# PowerSupplies.net
KiCad netlist of a schematic drawn in Altium Designer
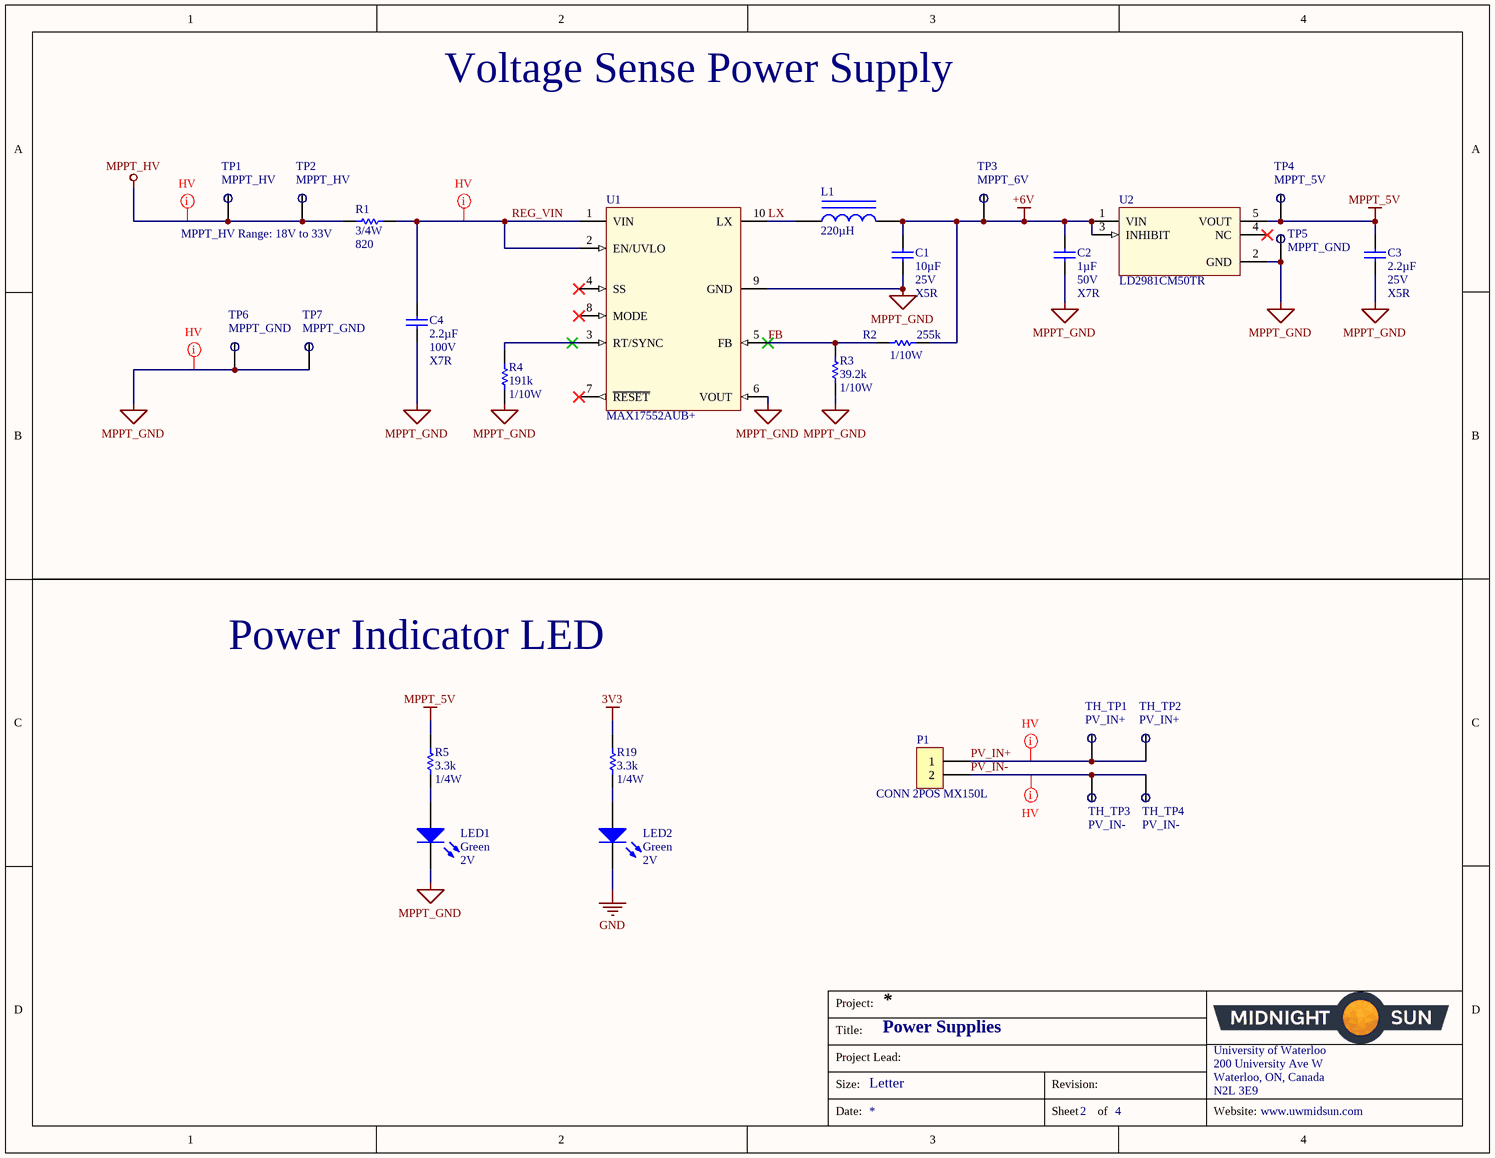
[diagram p0: PowerSupplies.SchDoc]

(export (version "E")
  (design (tool "Eeschema 10.0.6"))
  (components
    (comp (ref "C1")
      (value "CAP CER 10uF 25V 20% X5R 0603")
      (footprint "CAP, 0603")
      (description "10µF ±20% 25V Ceramic Capacitor X5R 0603 (1608 Metric)")
      (fields
        (field (name "TOLERANCE") "±20%")
        (field (name "CAPACITANCE") "10µF")
        (field (name "VOLTAGE") "25V")
        (field (name "TEMPERATURE COEFFICIENT") "X5R")
      )
      (libsource (lib "Schematic Diagrams") (part "CAP CER 10uF 25V 20% X5R 0603"))
    )
    (comp (ref "C2")
      (value "CAP CER 1UF 50V 10% X7R 0603")
      (footprint "CAP, 0603")
      (description "1µF ±10% 50V Ceramic Capacitor X7R 0603 (1608 Metric)")
      (fields
        (field (name "TOLERANCE") "±10%")
        (field (name "CAPACITANCE") "1µF")
        (field (name "VOLTAGE") "50V")
        (field (name "TEMPERATURE COEFFICIENT") "X7R")
      )
      (libsource (lib "Schematic Diagrams") (part "CAP CER 1UF 50V 10% X7R 0603"))
    )
    (comp (ref "C3")
      (value "CAP CER 2.2UF 25V 10% X5R 0603")
      (footprint "CAP, 0603")
      (description "2.2µF ±10% 25V Ceramic Capacitor X5R 0603 (1608 Metric)")
      (fields
        (field (name "TOLERANCE") "±10%")
        (field (name "CAPACITANCE") "2.2µF")
        (field (name "VOLTAGE") "25V")
        (field (name "TEMPERATURE COEFFICIENT") "X5R")
      )
      (libsource (lib "Schematic Diagrams") (part "CAP CER 2.2UF 25V 10% X5R 0603"))
    )
    (comp (ref "C4")
      (value "CAP CER 2.2UF 100V ±20% X7R 1206")
      (footprint "CAP, 1206")
      (description "2.2µF ±20% 100V Ceramic Capacitor X7R 1206 (3216 Metric)")
      (fields
        (field (name "TOLERANCE") "±20%")
        (field (name "CAPACITANCE") "2.2µF")
        (field (name "VOLTAGE") "100V")
        (field (name "TEMPERATURE COEFFICIENT") "X7R")
      )
      (libsource (lib "Schematic Diagrams") (part "CAP CER 2.2UF 100V ±20% X7R 1206"))
    )
    (comp (ref "L1")
      (value "IND 220uH 0.59A 20%")
      (footprint "INDP6060X23N")
      (description "220µH Shielded Inductor 590mA 834 mOhm Nonstandard")
      (fields (field (name "TOLERANCE") "±20%") (field (name "INDUCTANCE") "220µH"))
      (libsource (lib "Schematic Diagrams") (part "IND 220uH 0.59A 20%"))
    )
    (comp (ref "LED1")
      (value "LED GREEN CLEAR 2V 0603")
      (footprint "LED_0603")
      (description "Green 572nm LED Indication - Discrete 2V 0603 (1608 Metric)")
      (fields
        (field (name "MANUFACTURER") "Wurth Electronics Inc.")
        (field (name "MANUFACTURER PART NUMBER") "150060VS75000")
        (field (name "COLOR") "Green")
        (field (name "VOLTAGE - FORWARD (VF) (TYP)") "2V")
      )
      (libsource (lib "Schematic Diagrams") (part "LED GREEN CLEAR 2V 0603"))
    )
    (comp (ref "LED2")
      (value "LED GREEN CLEAR 2V 0603")
      (footprint "LED_0603")
      (description "Green 572nm LED Indication - Discrete 2V 0603 (1608 Metric)")
      (fields
        (field (name "MANUFACTURER") "Wurth Electronics Inc.")
        (field (name "MANUFACTURER PART NUMBER") "150060VS75000")
        (field (name "COLOR") "Green")
        (field (name "VOLTAGE - FORWARD (VF) (TYP)") "2V")
      )
      (libsource (lib "Schematic Diagrams") (part "LED GREEN CLEAR 2V 0603"))
    )
    (comp (ref "P1")
      (value "CONN 2POS MX150L")
      (footprint "CONN, 2POS MX150L")
      (description "Connector Header Panel Mount, Through Hole, Right Angle 2 position 0.230\" (5.84mm)")
      (fields
        (field (name "MANUFACTURER") "Molex, LLC")
        (field (name "MANUFACTURER PART NUMBER") "0194270109")
      )
      (libsource (lib "Schematic Diagrams") (part "CONN 2POS MX150L"))
    )
    (comp (ref "R1")
      (value "RES 820 OHM 5% 3/4W 2010")
      (footprint "RES 2010")
      (description "820 Ohms ±5% 0.75W, 3/4W Chip Resistor 2010 (5025 Metric) Automotive AEC-Q200 Thick Film")
      (fields
        (field (name "MANUFACTURER") "Stackpole Electronics Inc.")
        (field (name "MANUFACTURER PART NUMBER") "RMCF2010JT820R")
        (field (name "POWER") "3/4W")
        (field (name "RESISTANCE") "820")
      )
      (libsource (lib "Schematic Diagrams") (part "RES 820 OHM 5% 3/4W 2010"))
    )
    (comp (ref "R2")
      (value "RES 255K OHM 1% 1/10W 0603")
      (footprint "RES, 0603")
      (description "255k Ohm ±1% 0.1W, 1/10W Chip Resistor 0603 (1608 Metric) Moisture Resistant Thick Film")
      (fields
        (field (name "TOLERANCE") "±1%")
        (field (name "RESISTANCE (OHMS)") "255k")
        (field (name "POWER (WATTS)") "1/10W")
      )
      (libsource (lib "Schematic Diagrams") (part "RES 255K OHM 1% 1/10W 0603"))
    )
    (comp (ref "R3")
      (value "RES 39.2K OHM 1% 1/10W 0603")
      (footprint "RES, 0603")
      (description "39.2k Ohm ±1% 0.1W, 1/10W Chip Resistor 0603 (1608 Metric) Moisture Resistant Thick Film")
      (fields
        (field (name "TOLERANCE") "±1%")
        (field (name "RESISTANCE") "39.2k")
        (field (name "POWER") "1/10W")
      )
      (libsource (lib "Schematic Diagrams") (part "RES 39.2K OHM 1% 1/10W 0603"))
    )
    (comp (ref "R4")
      (value "RES 191K OHM 1% 1/10W 0603")
      (footprint "RES, 0603")
      (description "191k Ohm ±1% 0.1W, 1/10W Chip Resistor 0603 (1608 Metric) Moisture Resistant Thick Film")
      (fields
        (field (name "RESISTANCE") "191k")
        (field (name "TOLERANCE") "±1%")
        (field (name "POWER") "1/10W")
      )
      (libsource (lib "Schematic Diagrams") (part "RES 191K OHM 1% 1/10W 0603"))
    )
    (comp (ref "R5")
      (value "RES 3.3K OHM 1% 1/4W 0603")
      (footprint "RES, 0603")
      (fields
        (field (name "TOLERANCE") "±1%")
        (field (name "RESISTANCE") "3.3k")
        (field (name "POWER") "1/4W")
      )
      (libsource (lib "Schematic Diagrams") (part "RES 3.3K OHM 1% 1/4W 0603"))
    )
    (comp (ref "R19")
      (value "RES 3.3K OHM 1% 1/4W 0603")
      (footprint "RES, 0603")
      (fields
        (field (name "TOLERANCE") "±1%")
        (field (name "RESISTANCE") "3.3k")
        (field (name "POWER") "1/4W")
      )
      (libsource (lib "Schematic Diagrams") (part "RES 3.3K OHM 1% 1/4W 0603"))
    )
    (comp (ref "TH_TP1")
      (value "PV_IN+")
      (footprint "Thru Test Point")
      (libsource (lib "Schematic Diagrams") (part "Thru Test Point"))
    )
    (comp (ref "TH_TP2")
      (value "PV_IN+")
      (footprint "Thru Test Point")
      (libsource (lib "Schematic Diagrams") (part "Thru Test Point"))
    )
    (comp (ref "TH_TP3")
      (value "PV_IN-")
      (footprint "Thru Test Point")
      (libsource (lib "Schematic Diagrams") (part "Thru Test Point"))
    )
    (comp (ref "TH_TP4")
      (value "PV_IN-")
      (footprint "Thru Test Point")
      (libsource (lib "Schematic Diagrams") (part "Thru Test Point"))
    )
    (comp (ref "TP1")
      (value "MPPT_HV")
      (footprint "Thru Test Point")
      (libsource (lib "Schematic Diagrams") (part "Thru Test Point"))
    )
    (comp (ref "TP2")
      (value "MPPT_HV")
      (footprint "Thru Test Point")
      (libsource (lib "Schematic Diagrams") (part "Thru Test Point"))
    )
    (comp (ref "TP3")
      (value "MPPT_6V")
      (footprint "Thru Test Point")
      (libsource (lib "Schematic Diagrams") (part "Thru Test Point"))
    )
    (comp (ref "TP4")
      (value "MPPT_5V")
      (footprint "Thru Test Point")
      (libsource (lib "Schematic Diagrams") (part "Thru Test Point"))
    )
    (comp (ref "TP5")
      (value "MPPT_GND")
      (footprint "Thru Test Point")
      (libsource (lib "Schematic Diagrams") (part "Thru Test Point"))
    )
    (comp (ref "TP6")
      (value "MPPT_GND")
      (footprint "Thru Test Point")
      (libsource (lib "Schematic Diagrams") (part "Thru Test Point"))
    )
    (comp (ref "TP7")
      (value "MPPT_GND")
      (footprint "Thru Test Point")
      (libsource (lib "Schematic Diagrams") (part "Thru Test Point"))
    )
    (comp (ref "U1")
      (value "IC REG BUCK ADJ 0.1A 10UMAX")
      (footprint "TSSOP50P490X110-10N")
      (fields (field (name "MANUFACTURER PART NUMBER 1") "MAX17552AUB+"))
      (libsource (lib "Schematic Diagrams") (part "IC REG BUCK ADJ 0.1A 10UMAX"))
    )
    (comp (ref "U2")
      (value "IC REG LDO 5V 0.1A SOT23-5")
      (footprint "SOT95P280X145-5N")
      (description "Linear Voltage Regulator IC Positive Fixed Output 5V 100mA SOT-23-5")
      (fields (field (name "MANUFACTURER PART NUMBER 1") "LD2981CM50TR"))
      (libsource (lib "Schematic Diagrams") (part "IC REG LDO 5V 0.1A SOT23-5"))
    )
  )
  (nets
    (net (code "1") (name "+6V") (class "Default")
      (node (ref "C1") (pin "1") (pinfunction "1_1") (pintype "passive"))
      (node (ref "C2") (pin "1") (pinfunction "1_1") (pintype "passive"))
      (node (ref "L1") (pin "2") (pinfunction "2_2") (pintype "passive"))
      (node (ref "R2") (pin "2") (pinfunction "2_2") (pintype "passive"))
      (node (ref "TP3") (pin "TH_TP") (pinfunction "1_TH_TP") (pintype "passive"))
      (node (ref "U2") (pin "1") (pinfunction "VIN_1") (pintype "power_in"))
      (node (ref "U2") (pin "3") (pinfunction "INHIBIT_3") (pintype "input"))
    )
    (net (code "2") (name "/FB") (class "Default")
      (node (ref "R2") (pin "1") (pinfunction "1_1") (pintype "passive"))
      (node (ref "R3") (pin "1") (pinfunction "1_1") (pintype "passive"))
      (node (ref "U1") (pin "5") (pinfunction "FB_5") (pintype "input"))
    )
    (net (code "3") (name "/LX") (class "Default")
      (node (ref "L1") (pin "1") (pinfunction "1_1") (pintype "passive"))
      (node (ref "U1") (pin "10") (pinfunction "LX_10") (pintype "power_in"))
    )
    (net (code "4") (name "/PV_IN+") (class "Default")
      (node (ref "P1") (pin "1") (pinfunction "1_1") (pintype "passive"))
      (node (ref "TH_TP1") (pin "TH_TP") (pinfunction "1_TH_TP") (pintype "passive"))
      (node (ref "TH_TP2") (pin "TH_TP") (pinfunction "1_TH_TP") (pintype "passive"))
    )
    (net (code "5") (name "/PV_IN-") (class "Default")
      (node (ref "P1") (pin "2") (pinfunction "2_2") (pintype "passive"))
      (node (ref "TH_TP3") (pin "TH_TP") (pinfunction "1_TH_TP") (pintype "passive"))
      (node (ref "TH_TP4") (pin "TH_TP") (pinfunction "1_TH_TP") (pintype "passive"))
    )
    (net (code "6") (name "/REG_VIN") (class "Default")
      (node (ref "C4") (pin "1") (pinfunction "1_1") (pintype "passive"))
      (node (ref "R1") (pin "2") (pinfunction "2_2") (pintype "passive"))
      (node (ref "U1") (pin "1") (pinfunction "VIN_1") (pintype "power_in"))
      (node (ref "U1") (pin "2") (pinfunction "EN/UVLO_2") (pintype "input"))
    )
    (net (code "7") (name "3V3") (class "Default")
      (node (ref "R19") (pin "1") (pinfunction "1_1") (pintype "passive"))
    )
    (net (code "8") (name "GND") (class "Default")
      (node (ref "LED2") (pin "2") (pinfunction "K_2") (pintype "passive"))
    )
    (net (code "9") (name "MPPT_5V") (class "Default")
      (node (ref "C3") (pin "1") (pinfunction "1_1") (pintype "passive"))
      (node (ref "R5") (pin "1") (pinfunction "1_1") (pintype "passive"))
      (node (ref "TP4") (pin "TH_TP") (pinfunction "1_TH_TP") (pintype "passive"))
      (node (ref "U2") (pin "5") (pinfunction "VOUT_5") (pintype "power_in"))
    )
    (net (code "10") (name "MPPT_GND") (class "Default")
      (node (ref "C1") (pin "2") (pinfunction "2_2") (pintype "passive"))
      (node (ref "C2") (pin "2") (pinfunction "2_2") (pintype "passive"))
      (node (ref "C3") (pin "2") (pinfunction "2_2") (pintype "passive"))
      (node (ref "C4") (pin "2") (pinfunction "2_2") (pintype "passive"))
      (node (ref "LED1") (pin "2") (pinfunction "K_2") (pintype "passive"))
      (node (ref "R3") (pin "2") (pinfunction "2_2") (pintype "passive"))
      (node (ref "R4") (pin "2") (pinfunction "2_2") (pintype "passive"))
      (node (ref "TP5") (pin "TH_TP") (pinfunction "1_TH_TP") (pintype "passive"))
      (node (ref "TP6") (pin "TH_TP") (pinfunction "1_TH_TP") (pintype "passive"))
      (node (ref "TP7") (pin "TH_TP") (pinfunction "1_TH_TP") (pintype "passive"))
      (node (ref "U1") (pin "6") (pinfunction "VOUT_6") (pintype "input"))
      (node (ref "U1") (pin "9") (pinfunction "GND_9") (pintype "power_in"))
      (node (ref "U2") (pin "2") (pinfunction "GND_2") (pintype "power_in"))
    )
    (net (code "11") (name "MPPT_HV") (class "Default")
      (node (ref "R1") (pin "1") (pinfunction "1_1") (pintype "passive"))
      (node (ref "TP1") (pin "TH_TP") (pinfunction "1_TH_TP") (pintype "passive"))
      (node (ref "TP2") (pin "TH_TP") (pinfunction "1_TH_TP") (pintype "passive"))
    )
    (net (code "12") (name "Net-(LED1-A)") (class "Default")
      (node (ref "LED1") (pin "1") (pinfunction "A_1") (pintype "passive"))
      (node (ref "R5") (pin "2") (pinfunction "2_2") (pintype "passive"))
    )
    (net (code "13") (name "Net-(LED2-A)") (class "Default")
      (node (ref "LED2") (pin "1") (pinfunction "A_1") (pintype "passive"))
      (node (ref "R19") (pin "2") (pinfunction "2_2") (pintype "passive"))
    )
    (net (code "14") (name "Net-(U1-RT{slash}SYNC)") (class "Default")
      (node (ref "R4") (pin "1") (pinfunction "1_1") (pintype "passive"))
      (node (ref "U1") (pin "3") (pinfunction "RT/SYNC_3") (pintype "input"))
    )
    (net (code "15") (name "unconnected-(U1-MODE-Pad8)") (class "Default")
      (node (ref "U1") (pin "8") (pinfunction "MODE_8") (pintype "input+no_connect"))
    )
    (net (code "16") (name "unconnected-(U1-SS-Pad4)") (class "Default")
      (node (ref "U1") (pin "4") (pinfunction "SS_4") (pintype "input+no_connect"))
    )
    (net (code "17") (name "unconnected-(U1-~{RESET}-Pad7)") (class "Default")
      (node (ref "U1") (pin "7") (pinfunction "~{RESET}_7") (pintype "output+no_connect"))
    )
    (net (code "18") (name "unconnected-(U2-NC-Pad4)") (class "Default")
      (node (ref "U2") (pin "4") (pinfunction "NC_4") (pintype "passive+no_connect"))
    )
  )
)
